# PDM-S05-V00-TempSensing.net
KiCad netlist of a schematic drawn in Altium Designer
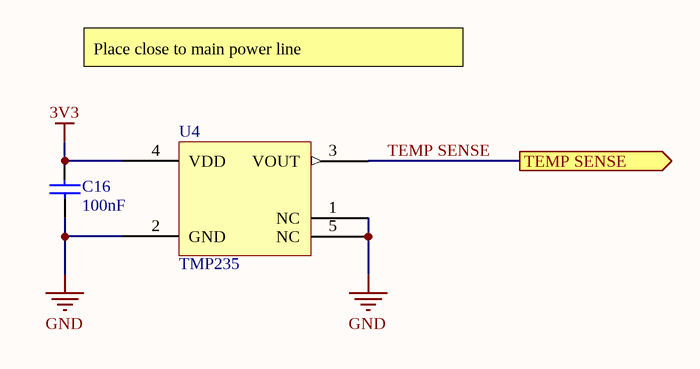
[diagram p0: PDM-S05-V00-TempSensing.SchDoc]

(export (version "E")
  (design (tool "Eeschema 10.0.6"))
  (components
    (comp (ref "C16")
      (value "100nF")
      (footprint "Cap_Ceramic_0603")
      (description "Capacitor, Ceramic, SMD, 100nF, 50V, 5%, X7R, 0603")
      (libsource (lib "StandardCapacitors") (part "100nF 50V 5% X7R 0603"))
    )
    (comp (ref "U4")
      (value "TMP235")
      (footprint "SC70")
      (description "TMP235, Low-Power, High-Accuracy Analog Output Temperature Sensor")
      (libsource (lib "PDM-CARD-SCHLib-V00") (part "TMP235"))
    )
  )
  (nets
    (net (code "1") (name "/TEMP SENSE") (class "Default")
      (node (ref "U4") (pin "3") (pinfunction "VOUT_3") (pintype "output"))
    )
    (net (code "2") (name "3V3") (class "Default")
      (node (ref "C16") (pin "2") (pinfunction "2_2") (pintype "passive"))
      (node (ref "U4") (pin "4") (pinfunction "VDD_4") (pintype "passive"))
    )
    (net (code "3") (name "GND") (class "Default")
      (node (ref "C16") (pin "1") (pinfunction "1_1") (pintype "passive"))
      (node (ref "U4") (pin "1") (pinfunction "NC_1") (pintype "passive"))
      (node (ref "U4") (pin "2") (pinfunction "GND_2") (pintype "passive"))
      (node (ref "U4") (pin "5") (pinfunction "NC_5") (pintype "passive"))
    )
  )
)
